# narwhal_1.net
KiCad netlist of a schematic drawn in Altium Designer
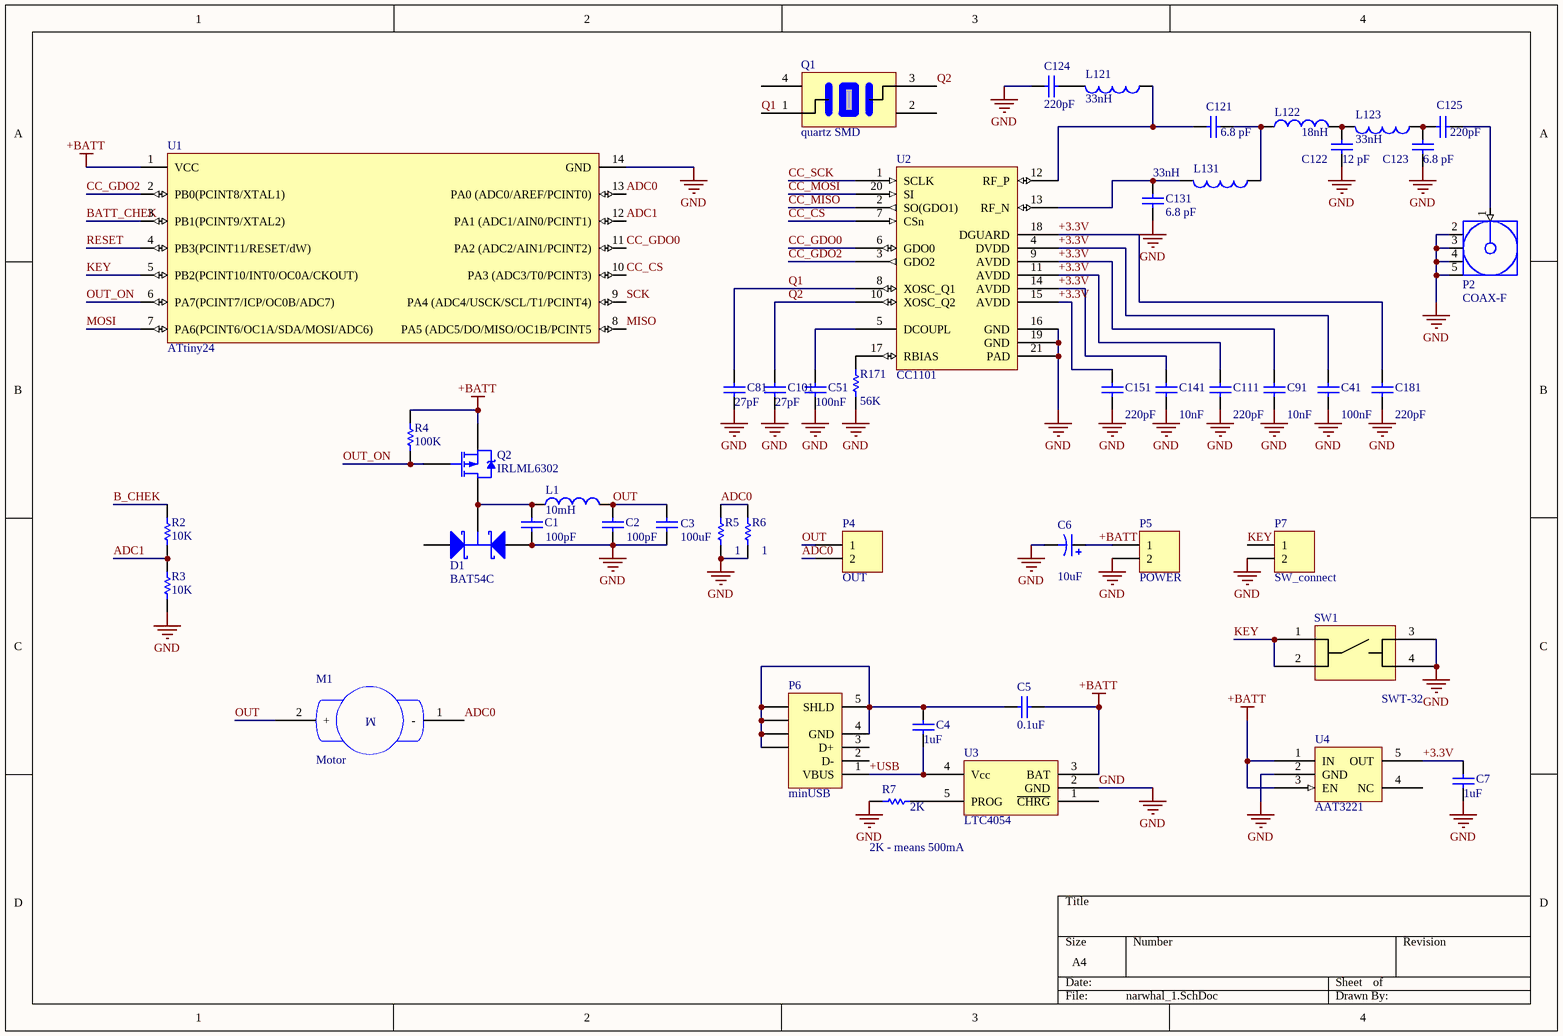
[diagram p0: narwhal_1.SchDoc]

(export (version "E")
  (design (tool "Eeschema 10.0.6"))
  (components
    (comp (ref "C1")
      (value "100pF")
      (footprint "1608[0603]A")
      (description "Capacitor (Semiconductor SIM Model)")
      (fields (field (name "PUBLISHER") "Altium Limited"))
      (libsource (lib "Miscellaneous Devices") (part "Cap Semi"))
    )
    (comp (ref "C2")
      (value "100pF")
      (footprint "2012[0805]A")
      (description "Capacitor (Semiconductor SIM Model)")
      (fields (field (name "PUBLISHER") "Altium Limited"))
      (libsource (lib "Miscellaneous Devices") (part "Cap Semi"))
    )
    (comp (ref "C3")
      (value "100uF")
      (footprint "1608[0603]")
      (description "Capacitor (Semiconductor SIM Model)")
      (fields (field (name "PUBLISHER") "Altium Limited"))
      (libsource (lib "Miscellaneous Devices") (part "Cap Semi"))
    )
    (comp (ref "C4")
      (value "1uF")
      (footprint "CAPC1608L")
      (description "Capacitor (Semiconductor SIM Model)")
      (fields (field (name "Comment") "Cap Semi") (field (name "PUBLISHER") "Altium Limited"))
      (libsource (lib "Miscellaneous Devices") (part "Cap Semi"))
    )
    (comp (ref "C5")
      (value "0.1uF")
      (footprint "CAPC1005L")
      (description "Capacitor (Semiconductor SIM Model)")
      (fields (field (name "Comment") "Cap Semi") (field (name "PUBLISHER") "Altium Limited"))
      (libsource (lib "Miscellaneous Devices") (part "Cap Semi"))
    )
    (comp (ref "C6")
      (value "10uF")
      (footprint "CAPC2012L")
      (description "Polarized Capacitor (Surface Mount)")
      (fields (field (name "Comment") "Cap Pol3") (field (name "PUBLISHER") "Altium Limited"))
      (libsource (lib "Miscellaneous Devices") (part "Cap Pol3"))
    )
    (comp (ref "C7")
      (value "1uF")
      (footprint "CAPC1608L")
      (description "Capacitor (Semiconductor SIM Model)")
      (fields (field (name "Comment") "Cap Semi") (field (name "PUBLISHER") "Altium Limited"))
      (libsource (lib "Miscellaneous Devices") (part "Cap Semi"))
    )
    (comp (ref "C41")
      (value "100nF")
      (footprint "CAPC1005L")
      (description "Capacitor (Semiconductor SIM Model)")
      (fields (field (name "Comment") "Cap Semi") (field (name "PUBLISHER") "Altium Limited"))
      (libsource (lib "Miscellaneous Devices") (part "Cap Semi"))
    )
    (comp (ref "C51")
      (value "100nF")
      (footprint "CAPC1005L")
      (description "Capacitor (Semiconductor SIM Model)")
      (fields (field (name "Comment") "Cap Semi") (field (name "PUBLISHER") "Altium Limited"))
      (libsource (lib "Miscellaneous Devices") (part "Cap Semi"))
    )
    (comp (ref "C81")
      (value "27pF")
      (footprint "CAPC1005L")
      (description "Capacitor (Semiconductor SIM Model)")
      (fields (field (name "Comment") "Cap Semi") (field (name "PUBLISHER") "Altium Limited"))
      (libsource (lib "Miscellaneous Devices") (part "Cap Semi"))
    )
    (comp (ref "C91")
      (value "10nF")
      (footprint "CAPC1005L")
      (description "Capacitor (Semiconductor SIM Model)")
      (fields (field (name "Comment") "Cap Semi") (field (name "PUBLISHER") "Altium Limited"))
      (libsource (lib "Miscellaneous Devices") (part "Cap Semi"))
    )
    (comp (ref "C101")
      (value "27pF")
      (footprint "CAPC1005L")
      (description "Capacitor (Semiconductor SIM Model)")
      (fields (field (name "Comment") "Cap Semi") (field (name "PUBLISHER") "Altium Limited"))
      (libsource (lib "Miscellaneous Devices") (part "Cap Semi"))
    )
    (comp (ref "C111")
      (value "220pF")
      (footprint "CAPC1005L")
      (description "Capacitor (Semiconductor SIM Model)")
      (fields (field (name "Comment") "Cap Semi") (field (name "PUBLISHER") "Altium Limited"))
      (libsource (lib "Miscellaneous Devices") (part "Cap Semi"))
    )
    (comp (ref "C121")
      (value "6.8 pF")
      (footprint "CAPC1005L")
      (description "Capacitor (Semiconductor SIM Model)")
      (fields (field (name "Comment") "Cap Semi") (field (name "PUBLISHER") "Altium Limited"))
      (libsource (lib "Miscellaneous Devices") (part "Cap Semi"))
    )
    (comp (ref "C122")
      (value "12 pF")
      (footprint "CAPC1005L")
      (description "Capacitor (Semiconductor SIM Model)")
      (fields (field (name "Comment") "Cap Semi") (field (name "PUBLISHER") "Altium Limited"))
      (libsource (lib "Miscellaneous Devices") (part "Cap Semi"))
    )
    (comp (ref "C123")
      (value "6.8 pF")
      (footprint "CAPC1005L")
      (description "Capacitor (Semiconductor SIM Model)")
      (fields (field (name "Comment") "Cap Semi") (field (name "PUBLISHER") "Altium Limited"))
      (libsource (lib "Miscellaneous Devices") (part "Cap Semi"))
    )
    (comp (ref "C124")
      (value "220pF")
      (footprint "CAPC1005L")
      (description "Capacitor (Semiconductor SIM Model)")
      (fields (field (name "Comment") "Cap Semi") (field (name "PUBLISHER") "Altium Limited"))
      (libsource (lib "Miscellaneous Devices") (part "Cap Semi"))
    )
    (comp (ref "C125")
      (value "220pF")
      (footprint "CAPC1005L")
      (description "Capacitor (Semiconductor SIM Model)")
      (fields (field (name "Comment") "Cap Semi") (field (name "PUBLISHER") "Altium Limited"))
      (libsource (lib "Miscellaneous Devices") (part "Cap Semi"))
    )
    (comp (ref "C131")
      (value "6.8 pF")
      (footprint "CAPC1005L")
      (description "Capacitor (Semiconductor SIM Model)")
      (fields (field (name "Comment") "Cap Semi") (field (name "PUBLISHER") "Altium Limited"))
      (libsource (lib "Miscellaneous Devices") (part "Cap Semi"))
    )
    (comp (ref "C141")
      (value "10nF")
      (footprint "CAPC1005L")
      (description "Capacitor (Semiconductor SIM Model)")
      (fields (field (name "Comment") "Cap Semi") (field (name "PUBLISHER") "Altium Limited"))
      (libsource (lib "Miscellaneous Devices") (part "Cap Semi"))
    )
    (comp (ref "C151")
      (value "220pF")
      (footprint "CAPC1005L")
      (description "Capacitor (Semiconductor SIM Model)")
      (fields (field (name "Comment") "Cap Semi") (field (name "PUBLISHER") "Altium Limited"))
      (libsource (lib "Miscellaneous Devices") (part "Cap Semi"))
    )
    (comp (ref "C181")
      (value "220pF")
      (footprint "CAPC1005L")
      (description "Capacitor (Semiconductor SIM Model)")
      (fields (field (name "Comment") "Cap Semi") (field (name "PUBLISHER") "Altium Limited"))
      (libsource (lib "Miscellaneous Devices") (part "Cap Semi"))
    )
    (comp (ref "D1")
      (value "BAT54C")
      (footprint "SOT23_N")
      (description "Schottky Barrier Double Diode")
      (fields (field (name "PUBLISHER") "Altium Limited"))
      (libsource (lib "Philips Discrete Diode - Schottky") (part "BAT54C"))
    )
    (comp (ref "L1")
      (value "10mH")
      (footprint "6332[2512]")
      (description "Inductor")
      (fields (field (name "PUBLISHER") "Altium Limited"))
      (libsource (lib "Miscellaneous Devices") (part "Inductor"))
    )
    (comp (ref "L121")
      (value "33nH")
      (footprint "INDC1005AL")
      (description "Inductor")
      (fields (field (name "PUBLISHER") "Altium Limited"))
      (libsource (lib "Miscellaneous Devices") (part "Inductor"))
    )
    (comp (ref "L122")
      (value "18nH")
      (footprint "INDC1005AL")
      (description "Inductor")
      (fields (field (name "PUBLISHER") "Altium Limited"))
      (libsource (lib "Miscellaneous Devices") (part "Inductor"))
    )
    (comp (ref "L123")
      (value "33nH")
      (footprint "INDC1005AL")
      (description "Inductor")
      (fields (field (name "PUBLISHER") "Altium Limited"))
      (libsource (lib "Miscellaneous Devices") (part "Inductor"))
    )
    (comp (ref "L131")
      (value "33nH")
      (footprint "INDC1005AL")
      (description "Inductor")
      (fields (field (name "PUBLISHER") "Altium Limited"))
      (libsource (lib "Miscellaneous Devices") (part "Inductor"))
    )
    (comp (ref "M1") (value "Motor") (footprint "Motor") (libsource (lib "uni_Library") (part "Motor")))
    (comp (ref "P2")
      (value "COAX-F")
      (footprint "MCX5.08-H5")
      (fields (field (name "PUBLISHER") "Altium Limited"))
      (libsource (lib "Miscellaneous Connectors") (part "COAX-F"))
    )
    (comp (ref "P4")
      (value "OUT")
      (footprint "HDR1X2H")
      (description "Header, 2-Pin, Right Angle")
      (fields (field (name "PUBLISHER") "Altium Limited"))
      (libsource (lib "Miscellaneous Connectors") (part "Header 2H"))
    )
    (comp (ref "P5")
      (value "POWER")
      (footprint "HDR1X2H")
      (description "Header, 2-Pin, Right Angle")
      (fields (field (name "PUBLISHER") "Altium Limited"))
      (libsource (lib "Miscellaneous Connectors") (part "Header 2H"))
    )
    (comp (ref "P6")
      (value "minUSB")
      (footprint "440479")
      (description "USB 2.0, Right Angle, SMT, A Type, Receptacle, 5 Position, Black")
      (fields (field (name "PUBLISHER") "Altium Limited"))
      (libsource (lib "AMP Serial Bus USB") (part "440478-2"))
    )
    (comp (ref "P7")
      (value "SW_connect")
      (footprint "HDR1X2")
      (description "Header, 2-Pin")
      (fields (field (name "PUBLISHER") "Altium Limited"))
      (libsource (lib "Miscellaneous Connectors") (part "Header 2"))
    )
    (comp (ref "Q1")
      (value "quartz SMD")
      (footprint "quartz_pattern")
      (description "в корпусе 0532")
      (libsource (lib "uni_Library") (part "qartz 0532"))
    )
    (comp (ref "Q2")
      (value "IRLML6302")
      (footprint "SOT-23")
      (description "HEXFET Power MOSFET")
      (fields (field (name "PUBLISHER") "Altium Limited"))
      (libsource (lib "IR Discrete MOSFET - Power") (part "IRLML6302"))
    )
    (comp (ref "R2")
      (value "10K")
      (footprint "RESC1005L")
      (description "Semiconductor Resistor")
      (fields (field (name "Comment") "Res Semi") (field (name "PUBLISHER") "Altium Limited"))
      (libsource (lib "Miscellaneous Devices") (part "Res Semi"))
    )
    (comp (ref "R3")
      (value "10K")
      (footprint "RESC1005L")
      (description "Semiconductor Resistor")
      (fields (field (name "Comment") "Res Semi") (field (name "PUBLISHER") "Altium Limited"))
      (libsource (lib "Miscellaneous Devices") (part "Res Semi"))
    )
    (comp (ref "R4")
      (value "100K")
      (footprint "RESC1005L")
      (description "Semiconductor Resistor")
      (fields (field (name "Comment") "Res Semi") (field (name "PUBLISHER") "Altium Limited"))
      (libsource (lib "Miscellaneous Devices") (part "Res Semi"))
    )
    (comp (ref "R5")
      (value "1")
      (footprint "1608[0603]A")
      (description "Semiconductor Resistor")
      (fields (field (name "PUBLISHER") "Altium Limited"))
      (libsource (lib "Miscellaneous Devices") (part "Res Semi"))
    )
    (comp (ref "R6")
      (value "1")
      (footprint "1608[0603]A")
      (description "Semiconductor Resistor")
      (fields (field (name "PUBLISHER") "Altium Limited"))
      (libsource (lib "Miscellaneous Devices") (part "Res Semi"))
    )
    (comp (ref "R7")
      (value "2K")
      (footprint "RESC1005L")
      (description "Semiconductor Resistor")
      (fields (field (name "Comment") "Res Semi") (field (name "PUBLISHER") "Altium Limited"))
      (libsource (lib "Miscellaneous Devices") (part "Res Semi"))
    )
    (comp (ref "R171")
      (value "56K")
      (footprint "RESC1005L")
      (description "Semiconductor Resistor")
      (fields (field (name "Comment") "Res Semi") (field (name "PUBLISHER") "Altium Limited"))
      (libsource (lib "Miscellaneous Devices") (part "Res Semi"))
    )
    (comp (ref "SW1")
      (value "SWT-32")
      (footprint "SWT-32 pattern")
      (description "Кнопка тактова , поверхностный монтаж")
      (libsource (lib "uni_Library") (part "SWT-32"))
    )
    (comp (ref "U1")
      (value "ATtiny24")
      (footprint "SOIC14_M")
      (description "8-Bit AVR Microcontroller with 1K Byte of Flash Memory")
      (fields (field (name "PUBLISHER") "Altium Limited"))
      (libsource (lib "Integrated_Library1") (part "ATtiny24"))
    )
    (comp (ref "U2")
      (value "CC1101")
      (footprint "QFN50P397X397X80-20N")
      (description "Low-Power Sub-1 GHz RF Transceiver")
      (libsource (lib "uni_Library") (part "CC1101"))
    )
    (comp (ref "U3")
      (value "LTC4054")
      (footprint "SOT95P270X100-5N")
      (description "Standalone Linear  Li-Ion Battery Charger with  Thermal Regulation in ThinSOT")
      (libsource (lib "uni_Library") (part "LTC4054"))
    )
    (comp (ref "U4")
      (value "AAT3221")
      (footprint "SOT95P280X145-5N")
      (description "PowerLinear NanoPower low   dropout (LDO) linear regulator.")
      (libsource (lib "uni_Library") (part "AAT3221"))
    )
  )
  (nets
    (net (code "1") (name "+BATT") (class "Default")
      (node (ref "C5") (pin "2") (pinfunction "2_2") (pintype "passive"))
      (node (ref "C6") (pin "1") (pinfunction "1_1") (pintype "passive"))
      (node (ref "P5") (pin "1") (pinfunction "1_1") (pintype "passive"))
      (node (ref "Q2") (pin "2") (pinfunction "S_2") (pintype "passive"))
      (node (ref "R4") (pin "1") (pinfunction "1_1") (pintype "passive"))
      (node (ref "U1") (pin "1") (pinfunction "VCC_1") (pintype "power_in"))
      (node (ref "U3") (pin "3") (pinfunction "BAT_3") (pintype "passive"))
      (node (ref "U4") (pin "1") (pinfunction "IN_1") (pintype "power_in"))
      (node (ref "U4") (pin "3") (pinfunction "EN_3") (pintype "input"))
    )
    (net (code "2") (name "/+3.3V") (class "Default")
      (node (ref "C111") (pin "2") (pinfunction "2_2") (pintype "passive"))
      (node (ref "C141") (pin "2") (pinfunction "2_2") (pintype "passive"))
      (node (ref "C151") (pin "2") (pinfunction "2_2") (pintype "passive"))
      (node (ref "C181") (pin "2") (pinfunction "2_2") (pintype "passive"))
      (node (ref "C41") (pin "2") (pinfunction "2_2") (pintype "passive"))
      (node (ref "C7") (pin "1") (pinfunction "1_1") (pintype "passive"))
      (node (ref "C91") (pin "2") (pinfunction "2_2") (pintype "passive"))
      (node (ref "U2") (pin "11") (pinfunction "AVDD_11") (pintype "power_in"))
      (node (ref "U2") (pin "14") (pinfunction "AVDD_14") (pintype "power_in"))
      (node (ref "U2") (pin "15") (pinfunction "AVDD_15") (pintype "power_in"))
      (node (ref "U2") (pin "18") (pinfunction "DGUARD_18") (pintype "power_in"))
      (node (ref "U2") (pin "4") (pinfunction "DVDD_4") (pintype "power_in"))
      (node (ref "U2") (pin "9") (pinfunction "AVDD_9") (pintype "power_in"))
      (node (ref "U4") (pin "5") (pinfunction "OUT_5") (pintype "power_in"))
    )
    (net (code "3") (name "/+USB") (class "Default")
      (node (ref "C4") (pin "2") (pinfunction "2_2") (pintype "passive"))
      (node (ref "P6") (pin "1") (pinfunction "VBUS_1") (pintype "power_in"))
      (node (ref "U3") (pin "4") (pinfunction "Vcc_4") (pintype "passive"))
    )
    (net (code "4") (name "/ADC0") (class "Default")
      (node (ref "M1") (pin "1") (pinfunction "-_1") (pintype "passive"))
      (node (ref "P4") (pin "2") (pinfunction "2_2") (pintype "passive"))
      (node (ref "R5") (pin "2") (pinfunction "2_2") (pintype "passive"))
      (node (ref "R6") (pin "2") (pinfunction "2_2") (pintype "passive"))
      (node (ref "U1") (pin "13") (pinfunction "PA0_(ADC0/AREF/PCINT0)_13") (pintype "bidirectional"))
    )
    (net (code "5") (name "/ADC1") (class "Default")
      (node (ref "R2") (pin "2") (pinfunction "2_2") (pintype "passive"))
      (node (ref "R3") (pin "1") (pinfunction "1_1") (pintype "passive"))
      (node (ref "U1") (pin "12") (pinfunction "PA1_(ADC1/AIN0/PCINT1)_12") (pintype "bidirectional"))
    )
    (net (code "6") (name "/BATT_CHEK") (class "Default")
      (node (ref "U1") (pin "3") (pinfunction "PB1(PCINT9/XTAL2)_3") (pintype "bidirectional"))
    )
    (net (code "7") (name "/B_CHEK") (class "Default")
      (node (ref "R2") (pin "1") (pinfunction "1_1") (pintype "passive"))
    )
    (net (code "8") (name "/CC_CS") (class "Default")
      (node (ref "U1") (pin "10") (pinfunction "PA3_(ADC3/T0/PCINT3)_10") (pintype "bidirectional"))
      (node (ref "U2") (pin "7") (pinfunction "CSn_7") (pintype "input"))
    )
    (net (code "9") (name "/CC_GDO0") (class "Default")
      (node (ref "U1") (pin "11") (pinfunction "PA2_(ADC2/AIN1/PCINT2)_11") (pintype "bidirectional"))
      (node (ref "U2") (pin "6") (pinfunction "GDO0_6") (pintype "bidirectional"))
    )
    (net (code "10") (name "/CC_GDO2") (class "Default")
      (node (ref "U1") (pin "2") (pinfunction "PB0(PCINT8/XTAL1)_2") (pintype "bidirectional"))
      (node (ref "U2") (pin "3") (pinfunction "GDO2_3") (pintype "output"))
    )
    (net (code "11") (name "/CC_MISO") (class "Default")
      (node (ref "U2") (pin "2") (pinfunction "SO(GDO1)_2") (pintype "output"))
    )
    (net (code "12") (name "/CC_MOSI") (class "Default")
      (node (ref "U2") (pin "20") (pinfunction "SI_20") (pintype "input"))
    )
    (net (code "13") (name "/CC_SCK") (class "Default")
      (node (ref "U2") (pin "1") (pinfunction "SCLK_1") (pintype "input"))
    )
    (net (code "14") (name "/KEY") (class "Default")
      (node (ref "P7") (pin "1") (pinfunction "1_1") (pintype "passive"))
      (node (ref "SW1") (pin "1") (pintype "passive"))
      (node (ref "SW1") (pin "2") (pintype "passive"))
      (node (ref "U1") (pin "5") (pinfunction "PB2(PCINT10/INT0/OC0A/CKOUT)_5") (pintype "bidirectional"))
    )
    (net (code "15") (name "/MISO") (class "Default")
      (node (ref "U1") (pin "8") (pinfunction "PA5_(ADC5/DO/MISO/OC1B/PCINT5_8") (pintype "bidirectional"))
    )
    (net (code "16") (name "/MOSI") (class "Default")
      (node (ref "U1") (pin "7") (pinfunction "PA6(PCINT6/OC1A/SDA/MOSI/ADC6)_7") (pintype "bidirectional"))
    )
    (net (code "17") (name "/OUT") (class "Default")
      (node (ref "C2") (pin "2") (pinfunction "2_2") (pintype "passive"))
      (node (ref "C3") (pin "2") (pinfunction "2_2") (pintype "passive"))
      (node (ref "L1") (pin "2") (pinfunction "2_2") (pintype "passive"))
      (node (ref "M1") (pin "2") (pinfunction "+_2") (pintype "passive"))
      (node (ref "P4") (pin "1") (pinfunction "1_1") (pintype "passive"))
    )
    (net (code "18") (name "/OUT_ON") (class "Default")
      (node (ref "Q2") (pin "1") (pinfunction "G_1") (pintype "passive"))
      (node (ref "R4") (pin "2") (pinfunction "2_2") (pintype "passive"))
      (node (ref "U1") (pin "6") (pinfunction "PA7(PCINT7/ICP/OC0B/ADC7)_6") (pintype "bidirectional"))
    )
    (net (code "19") (name "/Q1") (class "Default")
      (node (ref "C81") (pin "2") (pinfunction "2_2") (pintype "passive"))
      (node (ref "Q1") (pin "1") (pintype "passive"))
      (node (ref "U2") (pin "8") (pinfunction "XOSC_Q1_8") (pintype "bidirectional"))
    )
    (net (code "20") (name "/Q2") (class "Default")
      (node (ref "C101") (pin "2") (pinfunction "2_2") (pintype "passive"))
      (node (ref "Q1") (pin "3") (pintype "passive"))
      (node (ref "U2") (pin "10") (pinfunction "XOSC_Q2_10") (pintype "bidirectional"))
    )
    (net (code "21") (name "/RESET") (class "Default")
      (node (ref "U1") (pin "4") (pinfunction "PB3(PCINT11/RESET/dW)_4") (pintype "bidirectional"))
    )
    (net (code "22") (name "/SCK") (class "Default")
      (node (ref "U1") (pin "9") (pinfunction "PA4_(ADC4/USCK/SCL/T1/PCINT4)_9") (pintype "bidirectional"))
    )
    (net (code "23") (name "GND") (class "Default")
      (node (ref "C1") (pin "1") (pinfunction "1_1") (pintype "passive"))
      (node (ref "C101") (pin "1") (pinfunction "1_1") (pintype "passive"))
      (node (ref "C111") (pin "1") (pinfunction "1_1") (pintype "passive"))
      (node (ref "C122") (pin "1") (pinfunction "1_1") (pintype "passive"))
      (node (ref "C123") (pin "1") (pinfunction "1_1") (pintype "passive"))
      (node (ref "C124") (pin "2") (pinfunction "2_2") (pintype "passive"))
      (node (ref "C131") (pin "2") (pinfunction "2_2") (pintype "passive"))
      (node (ref "C141") (pin "1") (pinfunction "1_1") (pintype "passive"))
      (node (ref "C151") (pin "1") (pinfunction "1_1") (pintype "passive"))
      (node (ref "C181") (pin "1") (pinfunction "1_1") (pintype "passive"))
      (node (ref "C2") (pin "1") (pinfunction "1_1") (pintype "passive"))
      (node (ref "C3") (pin "1") (pinfunction "1_1") (pintype "passive"))
      (node (ref "C41") (pin "1") (pinfunction "1_1") (pintype "passive"))
      (node (ref "C51") (pin "1") (pinfunction "1_1") (pintype "passive"))
      (node (ref "C6") (pin "2") (pinfunction "2_2") (pintype "passive"))
      (node (ref "C7") (pin "2") (pinfunction "2_2") (pintype "passive"))
      (node (ref "C81") (pin "1") (pinfunction "1_1") (pintype "passive"))
      (node (ref "C91") (pin "1") (pinfunction "1_1") (pintype "passive"))
      (node (ref "D1") (pin "2") (pinfunction "A2_2") (pintype "passive"))
      (node (ref "P2") (pin "2") (pinfunction "GND_2") (pintype "power_in"))
      (node (ref "P2") (pin "3") (pinfunction "GND_3") (pintype "power_in"))
      (node (ref "P2") (pin "4") (pinfunction "GND_4") (pintype "power_in"))
      (node (ref "P2") (pin "5") (pinfunction "GND_5") (pintype "power_in"))
      (node (ref "P5") (pin "2") (pinfunction "2_2") (pintype "passive"))
      (node (ref "P7") (pin "2") (pinfunction "2_2") (pintype "passive"))
      (node (ref "R171") (pin "1") (pinfunction "1_1") (pintype "passive"))
      (node (ref "R3") (pin "2") (pinfunction "2_2") (pintype "passive"))
      (node (ref "R5") (pin "1") (pinfunction "1_1") (pintype "passive"))
      (node (ref "R6") (pin "1") (pinfunction "1_1") (pintype "passive"))
      (node (ref "R7") (pin "2") (pinfunction "2_2") (pintype "passive"))
      (node (ref "SW1") (pin "3") (pintype "passive"))
      (node (ref "SW1") (pin "4") (pintype "passive"))
      (node (ref "U1") (pin "14") (pinfunction "GND_14") (pintype "power_in"))
      (node (ref "U2") (pin "16") (pinfunction "GND_16") (pintype "power_in"))
      (node (ref "U2") (pin "19") (pinfunction "GND_19") (pintype "power_in"))
      (node (ref "U2") (pin "21") (pinfunction "PAD_21") (pintype "power_in"))
      (node (ref "U3") (pin "2") (pinfunction "GND_2") (pintype "passive"))
      (node (ref "U4") (pin "2") (pinfunction "GND_2") (pintype "power_in"))
    )
    (net (code "24") (name "Net-(C121-Pad1)") (class "Default")
      (node (ref "C121") (pin "1") (pinfunction "1_1") (pintype "passive"))
      (node (ref "L122") (pin "1") (pinfunction "1_1") (pintype "passive"))
      (node (ref "L131") (pin "1") (pinfunction "1_1") (pintype "passive"))
    )
    (net (code "25") (name "Net-(C122-Pad2)") (class "Default")
      (node (ref "C122") (pin "2") (pinfunction "2_2") (pintype "passive"))
      (node (ref "L122") (pin "2") (pinfunction "2_2") (pintype "passive"))
      (node (ref "L123") (pin "2") (pinfunction "2_2") (pintype "passive"))
    )
    (net (code "26") (name "Net-(C123-Pad2)") (class "Default")
      (node (ref "C123") (pin "2") (pinfunction "2_2") (pintype "passive"))
      (node (ref "C125") (pin "2") (pinfunction "2_2") (pintype "passive"))
      (node (ref "L123") (pin "1") (pinfunction "1_1") (pintype "passive"))
    )
    (net (code "27") (name "Net-(C124-Pad1)") (class "Default")
      (node (ref "C124") (pin "1") (pinfunction "1_1") (pintype "passive"))
      (node (ref "L121") (pin "2") (pinfunction "2_2") (pintype "passive"))
    )
    (net (code "28") (name "Net-(D1-K)") (class "Default")
      (node (ref "C1") (pin "2") (pinfunction "2_2") (pintype "passive"))
      (node (ref "D1") (pin "3") (pinfunction "K_3") (pintype "passive"))
      (node (ref "L1") (pin "1") (pinfunction "1_1") (pintype "passive"))
      (node (ref "Q2") (pin "3") (pinfunction "D_3") (pintype "passive"))
    )
    (net (code "29") (name "Net-(P2-Signal)") (class "Default")
      (node (ref "C125") (pin "1") (pinfunction "1_1") (pintype "passive"))
      (node (ref "P2") (pin "1") (pinfunction "Signal_1") (pintype "input"))
    )
    (net (code "30") (name "Net-(P6-GND)") (class "Default")
      (node (ref "C4") (pin "1") (pinfunction "1_1") (pintype "passive"))
      (node (ref "C5") (pin "1") (pinfunction "1_1") (pintype "passive"))
      (node (ref "P6") (pin "4") (pinfunction "GND_4") (pintype "power_in"))
      (node (ref "P6") (pin "5") (pinfunction "SHLD_5") (pintype "passive"))
      (node (ref "P6") (pin "6") (pinfunction "SHLD_6") (pintype "passive"))
      (node (ref "P6") (pin "7") (pinfunction "SHLD_7") (pintype "passive"))
      (node (ref "P6") (pin "8") (pinfunction "SHLD_8") (pintype "passive"))
      (node (ref "P6") (pin "9") (pinfunction "SHLD_9") (pintype "passive"))
    )
    (net (code "31") (name "Net-(U2-DCOUPL)") (class "Default")
      (node (ref "C51") (pin "2") (pinfunction "2_2") (pintype "passive"))
      (node (ref "U2") (pin "5") (pinfunction "DCOUPL_5") (pintype "power_in"))
    )
    (net (code "32") (name "Net-(U2-RBIAS)") (class "Default")
      (node (ref "R171") (pin "2") (pinfunction "2_2") (pintype "passive"))
      (node (ref "U2") (pin "17") (pinfunction "RBIAS_17") (pintype "bidirectional"))
    )
    (net (code "33") (name "Net-(U2-RF_N)") (class "Default")
      (node (ref "C131") (pin "1") (pinfunction "1_1") (pintype "passive"))
      (node (ref "L131") (pin "2") (pinfunction "2_2") (pintype "passive"))
      (node (ref "U2") (pin "13") (pinfunction "RF_N_13") (pintype "bidirectional"))
    )
    (net (code "34") (name "Net-(U2-RF_P)") (class "Default")
      (node (ref "C121") (pin "2") (pinfunction "2_2") (pintype "passive"))
      (node (ref "L121") (pin "1") (pinfunction "1_1") (pintype "passive"))
      (node (ref "U2") (pin "12") (pinfunction "RF_P_12") (pintype "bidirectional"))
    )
    (net (code "35") (name "Net-(U3-PROG)") (class "Default")
      (node (ref "R7") (pin "1") (pinfunction "1_1") (pintype "passive"))
      (node (ref "U3") (pin "5") (pinfunction "PROG_5") (pintype "passive"))
    )
    (net (code "36") (name "unconnected-(D1-A1-Pad1)") (class "Default")
      (node (ref "D1") (pin "1") (pinfunction "A1_1") (pintype "passive"))
    )
    (net (code "37") (name "unconnected-(P6-D+-Pad3)") (class "Default")
      (node (ref "P6") (pin "3") (pinfunction "D+_3") (pintype "passive"))
    )
    (net (code "38") (name "unconnected-(P6-D--Pad2)") (class "Default")
      (node (ref "P6") (pin "2") (pinfunction "D-_2") (pintype "passive"))
    )
    (net (code "39") (name "unconnected-(Q1-Pad2)") (class "Default")
      (node (ref "Q1") (pin "2") (pintype "passive"))
    )
    (net (code "40") (name "unconnected-(Q1-Pad4)") (class "Default")
      (node (ref "Q1") (pin "4") (pintype "passive"))
    )
    (net (code "41") (name "unconnected-(U3-~{CHRG}-Pad1)") (class "Default")
      (node (ref "U3") (pin "1") (pinfunction "~{CHRG}_1") (pintype "passive"))
    )
    (net (code "42") (name "unconnected-(U4-NC-Pad4)") (class "Default")
      (node (ref "U4") (pin "4") (pinfunction "NC_4") (pintype "passive"))
    )
  )
)
